# Support.net
KiCad netlist of a schematic drawn in Altium Designer
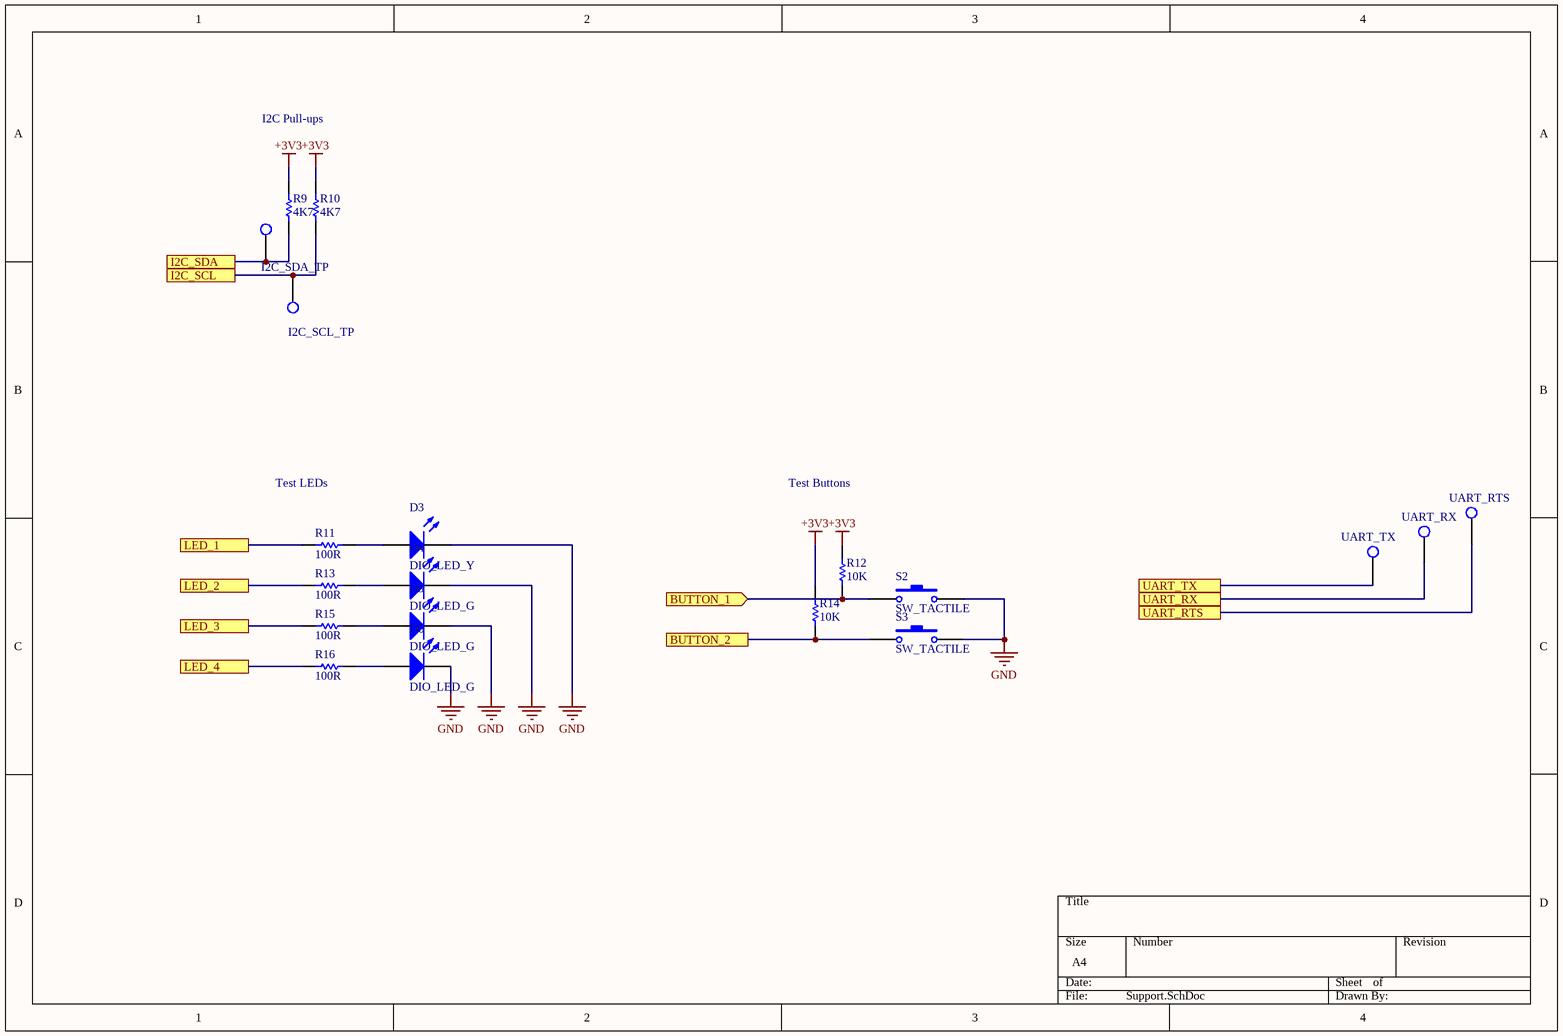
[diagram p0: Support.SchDoc]

(export (version "E")
  (design (tool "Eeschema 10.0.6"))
  (components
    (comp (ref "D3")
      (value "DIO_LED_Y")
      (footprint "LED_0805_LINE")
      (description "LED YELLOW DIFFUSED 0805 SMD")
      (fields (field (name "PART NUMBER") "LY R976-PS-36") (field (name "MANUFACTURER") "OSRAM"))
      (libsource (lib "UWRT_Schematic_Library_2019") (part "DIO_LED_Y"))
    )
    (comp (ref "D4")
      (value "DIO_LED_G")
      (footprint "LED_0805_LINE")
      (description "LED GREEN DIFFUSED 0805 SMD")
      (fields (field (name "PART NUMBER") "LG R971-KN-1") (field (name "MANUFACTURER") "OSRAM"))
      (libsource (lib "UWRT_Schematic_Library_2019") (part "DIO_LED_G"))
    )
    (comp (ref "D5")
      (value "DIO_LED_G")
      (footprint "LED_0805_LINE")
      (description "LED GREEN DIFFUSED 0805 SMD")
      (fields (field (name "PART NUMBER") "LG R971-KN-1") (field (name "MANUFACTURER") "OSRAM"))
      (libsource (lib "UWRT_Schematic_Library_2019") (part "DIO_LED_G"))
    )
    (comp (ref "D6")
      (value "DIO_LED_G")
      (footprint "LED_0805_LINE")
      (description "LED GREEN DIFFUSED 0805 SMD")
      (fields (field (name "PART NUMBER") "LG R971-KN-1") (field (name "MANUFACTURER") "OSRAM"))
      (libsource (lib "UWRT_Schematic_Library_2019") (part "DIO_LED_G"))
    )
    (comp (ref "R9")
      (value "4K7")
      (footprint "RESC0603(1608)_N")
      (description "RES SMD 4.7K OHM 5% 1/10W 0603")
      (fields (field (name "MANUFACTURER") "Yageo") (field (name "TOLERANCE") "5%"))
      (libsource (lib "UWRT_Schematic_Library_2019") (part "RES_4K7_0603"))
    )
    (comp (ref "R10")
      (value "4K7")
      (footprint "RESC0603(1608)_N")
      (description "RES SMD 4.7K OHM 5% 1/10W 0603")
      (fields (field (name "MANUFACTURER") "Yageo") (field (name "TOLERANCE") "5%"))
      (libsource (lib "UWRT_Schematic_Library_2019") (part "RES_4K7_0603"))
    )
    (comp (ref "R11")
      (value "100R")
      (footprint "RESC0603(1608)_N")
      (description "RES SMD 100 OHM 1% 1/10W 0603")
      (fields (field (name "MANUFACTURER") "Yageo") (field (name "TOLERANCE") "1%"))
      (libsource (lib "UWRT_Schematic_Library_2019") (part "RES_100R_0603"))
    )
    (comp (ref "R12")
      (value "10K")
      (footprint "RESC0603(1608)_N")
      (description "RES SMD 10K OHM 5% 1/10W 0603")
      (fields (field (name "MANUFACTURER") "Yageo") (field (name "TOLERANCE") "5%"))
      (libsource (lib "UWRT_Schematic_Library_2019") (part "RES_10K_0603"))
    )
    (comp (ref "R13")
      (value "100R")
      (footprint "RESC0603(1608)_N")
      (description "RES SMD 100 OHM 1% 1/10W 0603")
      (fields (field (name "MANUFACTURER") "Yageo") (field (name "TOLERANCE") "1%"))
      (libsource (lib "UWRT_Schematic_Library_2019") (part "RES_100R_0603"))
    )
    (comp (ref "R14")
      (value "10K")
      (footprint "RESC0603(1608)_N")
      (description "RES SMD 10K OHM 5% 1/10W 0603")
      (fields (field (name "MANUFACTURER") "Yageo") (field (name "TOLERANCE") "5%"))
      (libsource (lib "UWRT_Schematic_Library_2019") (part "RES_10K_0603"))
    )
    (comp (ref "R15")
      (value "100R")
      (footprint "RESC0603(1608)_N")
      (description "RES SMD 100 OHM 1% 1/10W 0603")
      (fields (field (name "MANUFACTURER") "Yageo") (field (name "TOLERANCE") "1%"))
      (libsource (lib "UWRT_Schematic_Library_2019") (part "RES_100R_0603"))
    )
    (comp (ref "R16")
      (value "100R")
      (footprint "RESC0603(1608)_N")
      (description "RES SMD 100 OHM 1% 1/10W 0603")
      (fields (field (name "MANUFACTURER") "Yageo") (field (name "TOLERANCE") "1%"))
      (libsource (lib "UWRT_Schematic_Library_2019") (part "RES_100R_0603"))
    )
    (comp (ref "S2")
      (value "SW_TACTILE")
      (footprint "B3U-1100P")
      (description "Tactile Switch (Grey)")
      (fields
        (field (name "MANUFACTURER PART NUMBER") "B3U-1100P")
        (field (name "DIGIKEY PART NUMBER") "SW1021TR-ND")
      )
      (libsource (lib "UWRT_Schematic_Library_2019") (part "SW_TACTILE"))
    )
    (comp (ref "S3")
      (value "SW_TACTILE")
      (footprint "B3U-1100P")
      (description "Tactile Switch (Grey)")
      (fields
        (field (name "MANUFACTURER PART NUMBER") "B3U-1100P")
        (field (name "DIGIKEY PART NUMBER") "SW1021TR-ND")
      )
      (libsource (lib "UWRT_Schematic_Library_2019") (part "SW_TACTILE"))
    )
    (comp (ref "TP7")
      (value "I2C_SDA_TP")
      (footprint "TESTPOINT_LOOP")
      (libsource (lib "UWRT_Schematic_Library_2019") (part "TESTPOINT_LOOP"))
    )
    (comp (ref "TP8")
      (value "I2C_SCL_TP")
      (footprint "TESTPOINT_LOOP")
      (libsource (lib "UWRT_Schematic_Library_2019") (part "TESTPOINT_LOOP"))
    )
    (comp (ref "TP9")
      (value "UART_RTS")
      (footprint "TESTPOINT_LOOP")
      (libsource (lib "UWRT_Schematic_Library_2019") (part "TESTPOINT_LOOP"))
    )
    (comp (ref "TP10")
      (value "UART_RX")
      (footprint "TESTPOINT_LOOP")
      (libsource (lib "UWRT_Schematic_Library_2019") (part "TESTPOINT_LOOP"))
    )
    (comp (ref "TP11")
      (value "UART_TX")
      (footprint "TESTPOINT_LOOP")
      (libsource (lib "UWRT_Schematic_Library_2019") (part "TESTPOINT_LOOP"))
    )
  )
  (nets
    (net (code "1") (name "+3V3") (class "Default")
      (node (ref "R10") (pin "2") (pinfunction "2_2") (pintype "passive"))
      (node (ref "R12") (pin "2") (pinfunction "2_2") (pintype "passive"))
      (node (ref "R14") (pin "1") (pinfunction "1_1") (pintype "passive"))
      (node (ref "R9") (pin "2") (pinfunction "2_2") (pintype "passive"))
    )
    (net (code "2") (name "/BUTTON_1") (class "Default")
      (node (ref "R12") (pin "1") (pinfunction "1_1") (pintype "passive"))
      (node (ref "S2") (pin "1") (pinfunction "1_1") (pintype "passive"))
    )
    (net (code "3") (name "/BUTTON_2") (class "Default")
      (node (ref "R14") (pin "2") (pinfunction "2_2") (pintype "passive"))
      (node (ref "S3") (pin "1") (pinfunction "1_1") (pintype "passive"))
    )
    (net (code "4") (name "/I2C_SCL") (class "Default")
      (node (ref "R10") (pin "1") (pinfunction "1_1") (pintype "passive"))
      (node (ref "TP8") (pin "1") (pinfunction "=value_1") (pintype "passive"))
    )
    (net (code "5") (name "/I2C_SDA") (class "Default")
      (node (ref "R9") (pin "1") (pinfunction "1_1") (pintype "passive"))
      (node (ref "TP7") (pin "1") (pinfunction "=value_1") (pintype "passive"))
    )
    (net (code "6") (name "/LED_1") (class "Default")
      (node (ref "R11") (pin "1") (pinfunction "1_1") (pintype "passive"))
    )
    (net (code "7") (name "/LED_2") (class "Default")
      (node (ref "R13") (pin "1") (pinfunction "1_1") (pintype "passive"))
    )
    (net (code "8") (name "/LED_3") (class "Default")
      (node (ref "R15") (pin "1") (pinfunction "1_1") (pintype "passive"))
    )
    (net (code "9") (name "/LED_4") (class "Default")
      (node (ref "R16") (pin "1") (pinfunction "1_1") (pintype "passive"))
    )
    (net (code "10") (name "/UART_RTS") (class "Default")
      (node (ref "TP9") (pin "1") (pinfunction "=value_1") (pintype "passive"))
    )
    (net (code "11") (name "/UART_RX") (class "Default")
      (node (ref "TP10") (pin "1") (pinfunction "=value_1") (pintype "passive"))
    )
    (net (code "12") (name "/UART_TX") (class "Default")
      (node (ref "TP11") (pin "1") (pinfunction "=value_1") (pintype "passive"))
    )
    (net (code "13") (name "GND") (class "Default")
      (node (ref "D3") (pin "2") (pinfunction "K_2") (pintype "passive"))
      (node (ref "D4") (pin "2") (pinfunction "K_2") (pintype "passive"))
      (node (ref "D5") (pin "2") (pinfunction "K_2") (pintype "passive"))
      (node (ref "D6") (pin "2") (pinfunction "K_2") (pintype "passive"))
      (node (ref "S2") (pin "2") (pinfunction "2_2") (pintype "passive"))
      (node (ref "S3") (pin "2") (pinfunction "2_2") (pintype "passive"))
    )
    (net (code "14") (name "Net-(D3-A)") (class "Default")
      (node (ref "D3") (pin "1") (pinfunction "A_1") (pintype "passive"))
      (node (ref "R11") (pin "2") (pinfunction "2_2") (pintype "passive"))
    )
    (net (code "15") (name "Net-(D4-A)") (class "Default")
      (node (ref "D4") (pin "1") (pinfunction "A_1") (pintype "passive"))
      (node (ref "R13") (pin "2") (pinfunction "2_2") (pintype "passive"))
    )
    (net (code "16") (name "Net-(D5-A)") (class "Default")
      (node (ref "D5") (pin "1") (pinfunction "A_1") (pintype "passive"))
      (node (ref "R15") (pin "2") (pinfunction "2_2") (pintype "passive"))
    )
    (net (code "17") (name "Net-(D6-A)") (class "Default")
      (node (ref "D6") (pin "1") (pinfunction "A_1") (pintype "passive"))
      (node (ref "R16") (pin "2") (pinfunction "2_2") (pintype "passive"))
    )
  )
)
